# 2_waffling60-MX_matrix.net
KiCad netlist of a schematic drawn in Altium Designer
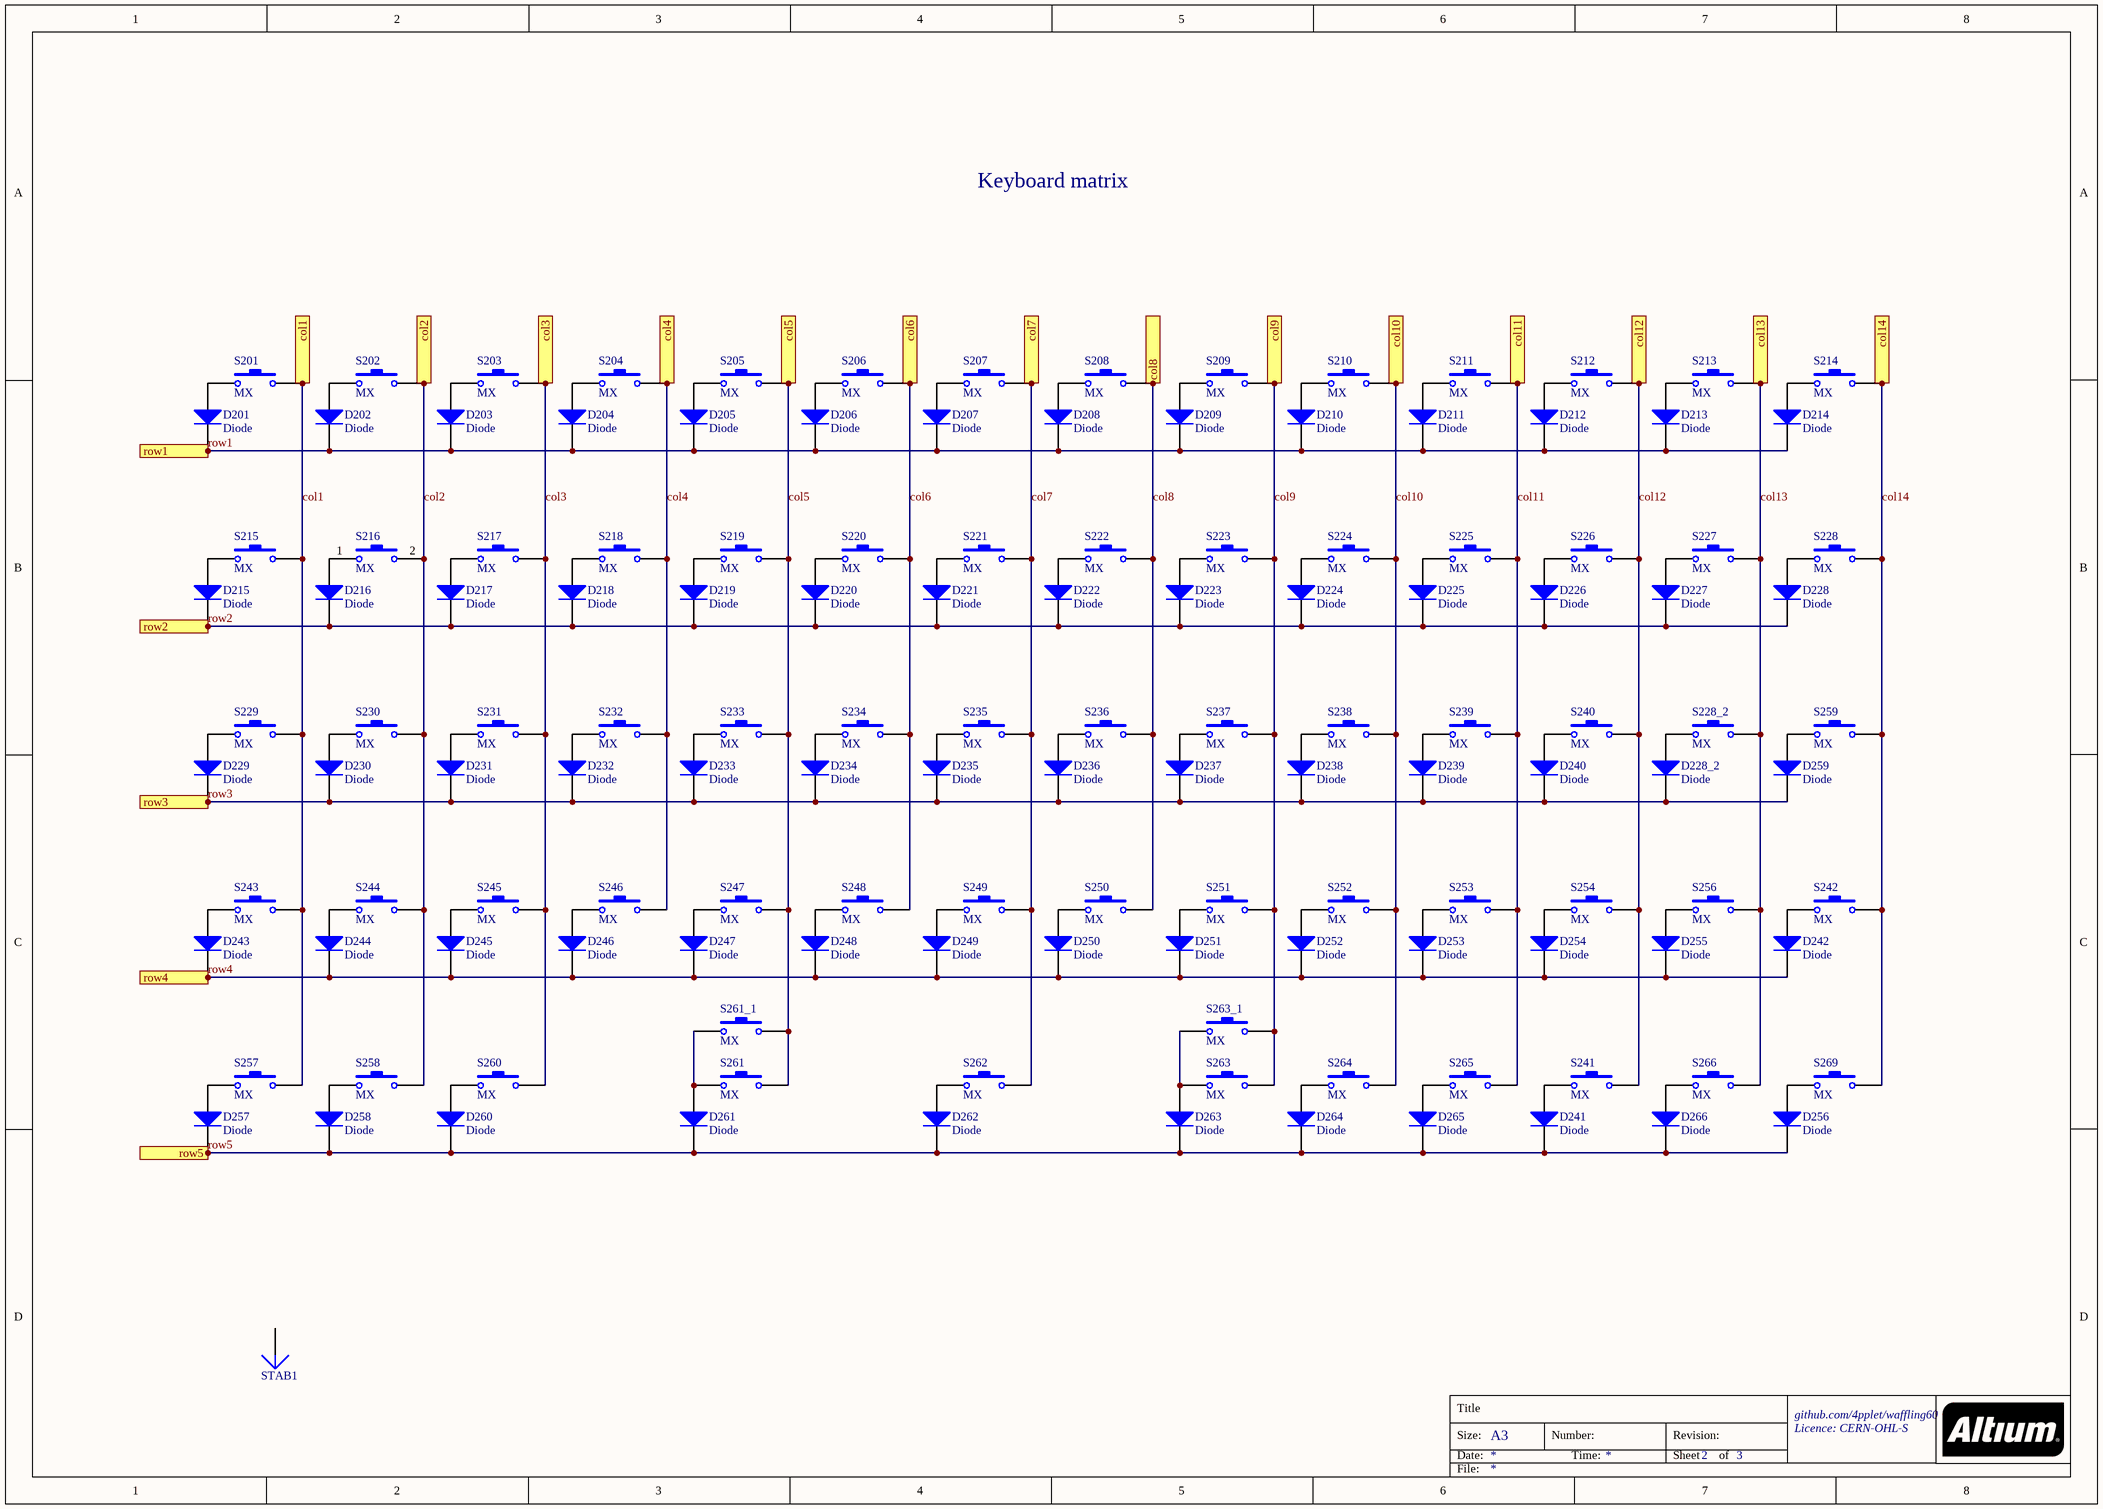
[diagram p0: 2_waffling60-MX_matrix.SchDoc]

(export (version "E")
  (design (tool "Eeschema 10.0.6"))
  (components
    (comp (ref "D201")
      (value "Diode")
      (footprint "SOD-123")
      (description "Default Diode")
      (fields (field (name "LCSC PART #") "C81598") (field (name "MRF.PART") "1N4148W"))
      (libsource (lib "Miscellaneous Devices") (part "Diode"))
    )
    (comp (ref "D202")
      (value "Diode")
      (footprint "SOD-123")
      (description "Default Diode")
      (fields (field (name "LCSC PART #") "C81598") (field (name "MRF.PART") "1N4148W"))
      (libsource (lib "Miscellaneous Devices") (part "Diode"))
    )
    (comp (ref "D203")
      (value "Diode")
      (footprint "SOD-123")
      (description "Default Diode")
      (fields (field (name "LCSC PART #") "C81598") (field (name "MRF.PART") "1N4148W"))
      (libsource (lib "Miscellaneous Devices") (part "Diode"))
    )
    (comp (ref "D204")
      (value "Diode")
      (footprint "SOD-123")
      (description "Default Diode")
      (fields (field (name "LCSC PART #") "C81598") (field (name "MRF.PART") "1N4148W"))
      (libsource (lib "Miscellaneous Devices") (part "Diode"))
    )
    (comp (ref "D205")
      (value "Diode")
      (footprint "SOD-123")
      (description "Default Diode")
      (fields (field (name "LCSC PART #") "C81598") (field (name "MRF.PART") "1N4148W"))
      (libsource (lib "Miscellaneous Devices") (part "Diode"))
    )
    (comp (ref "D206")
      (value "Diode")
      (footprint "SOD-123")
      (description "Default Diode")
      (fields (field (name "LCSC PART #") "C81598") (field (name "MRF.PART") "1N4148W"))
      (libsource (lib "Miscellaneous Devices") (part "Diode"))
    )
    (comp (ref "D207")
      (value "Diode")
      (footprint "SOD-123")
      (description "Default Diode")
      (fields (field (name "LCSC PART #") "C81598") (field (name "MRF.PART") "1N4148W"))
      (libsource (lib "Miscellaneous Devices") (part "Diode"))
    )
    (comp (ref "D208")
      (value "Diode")
      (footprint "SOD-123")
      (description "Default Diode")
      (fields (field (name "LCSC PART #") "C81598") (field (name "MRF.PART") "1N4148W"))
      (libsource (lib "Miscellaneous Devices") (part "Diode"))
    )
    (comp (ref "D209")
      (value "Diode")
      (footprint "SOD-123")
      (description "Default Diode")
      (fields (field (name "LCSC PART #") "C81598") (field (name "MRF.PART") "1N4148W"))
      (libsource (lib "Miscellaneous Devices") (part "Diode"))
    )
    (comp (ref "D210")
      (value "Diode")
      (footprint "SOD-123")
      (description "Default Diode")
      (fields (field (name "LCSC PART #") "C81598") (field (name "MRF.PART") "1N4148W"))
      (libsource (lib "Miscellaneous Devices") (part "Diode"))
    )
    (comp (ref "D211")
      (value "Diode")
      (footprint "SOD-123")
      (description "Default Diode")
      (fields (field (name "LCSC PART #") "C81598") (field (name "MRF.PART") "1N4148W"))
      (libsource (lib "Miscellaneous Devices") (part "Diode"))
    )
    (comp (ref "D212")
      (value "Diode")
      (footprint "SOD-123")
      (description "Default Diode")
      (fields (field (name "LCSC PART #") "C81598") (field (name "MRF.PART") "1N4148W"))
      (libsource (lib "Miscellaneous Devices") (part "Diode"))
    )
    (comp (ref "D213")
      (value "Diode")
      (footprint "SOD-123")
      (description "Default Diode")
      (fields (field (name "LCSC PART #") "C81598") (field (name "MRF.PART") "1N4148W"))
      (libsource (lib "Miscellaneous Devices") (part "Diode"))
    )
    (comp (ref "D214")
      (value "Diode")
      (footprint "SOD-123")
      (description "Default Diode")
      (fields (field (name "LCSC PART #") "C81598") (field (name "MRF.PART") "1N4148W"))
      (libsource (lib "Miscellaneous Devices") (part "Diode"))
    )
    (comp (ref "D215")
      (value "Diode")
      (footprint "SOD-123")
      (description "Default Diode")
      (fields (field (name "LCSC PART #") "C81598") (field (name "MRF.PART") "1N4148W"))
      (libsource (lib "Miscellaneous Devices") (part "Diode"))
    )
    (comp (ref "D216")
      (value "Diode")
      (footprint "SOD-123")
      (description "Default Diode")
      (fields (field (name "LCSC PART #") "C81598") (field (name "MRF.PART") "1N4148W"))
      (libsource (lib "Miscellaneous Devices") (part "Diode"))
    )
    (comp (ref "D217")
      (value "Diode")
      (footprint "SOD-123")
      (description "Default Diode")
      (fields (field (name "LCSC PART #") "C81598") (field (name "MRF.PART") "1N4148W"))
      (libsource (lib "Miscellaneous Devices") (part "Diode"))
    )
    (comp (ref "D218")
      (value "Diode")
      (footprint "SOD-123")
      (description "Default Diode")
      (fields (field (name "LCSC PART #") "C81598") (field (name "MRF.PART") "1N4148W"))
      (libsource (lib "Miscellaneous Devices") (part "Diode"))
    )
    (comp (ref "D219")
      (value "Diode")
      (footprint "SOD-123")
      (description "Default Diode")
      (fields (field (name "LCSC PART #") "C81598") (field (name "MRF.PART") "1N4148W"))
      (libsource (lib "Miscellaneous Devices") (part "Diode"))
    )
    (comp (ref "D220")
      (value "Diode")
      (footprint "SOD-123")
      (description "Default Diode")
      (fields (field (name "LCSC PART #") "C81598") (field (name "MRF.PART") "1N4148W"))
      (libsource (lib "Miscellaneous Devices") (part "Diode"))
    )
    (comp (ref "D221")
      (value "Diode")
      (footprint "SOD-123")
      (description "Default Diode")
      (fields (field (name "LCSC PART #") "C81598") (field (name "MRF.PART") "1N4148W"))
      (libsource (lib "Miscellaneous Devices") (part "Diode"))
    )
    (comp (ref "D222")
      (value "Diode")
      (footprint "SOD-123")
      (description "Default Diode")
      (fields (field (name "LCSC PART #") "C81598") (field (name "MRF.PART") "1N4148W"))
      (libsource (lib "Miscellaneous Devices") (part "Diode"))
    )
    (comp (ref "D223")
      (value "Diode")
      (footprint "SOD-123")
      (description "Default Diode")
      (fields (field (name "LCSC PART #") "C81598") (field (name "MRF.PART") "1N4148W"))
      (libsource (lib "Miscellaneous Devices") (part "Diode"))
    )
    (comp (ref "D224")
      (value "Diode")
      (footprint "SOD-123")
      (description "Default Diode")
      (fields (field (name "LCSC PART #") "C81598") (field (name "MRF.PART") "1N4148W"))
      (libsource (lib "Miscellaneous Devices") (part "Diode"))
    )
    (comp (ref "D225")
      (value "Diode")
      (footprint "SOD-123")
      (description "Default Diode")
      (fields (field (name "LCSC PART #") "C81598") (field (name "MRF.PART") "1N4148W"))
      (libsource (lib "Miscellaneous Devices") (part "Diode"))
    )
    (comp (ref "D226")
      (value "Diode")
      (footprint "SOD-123")
      (description "Default Diode")
      (fields (field (name "LCSC PART #") "C81598") (field (name "MRF.PART") "1N4148W"))
      (libsource (lib "Miscellaneous Devices") (part "Diode"))
    )
    (comp (ref "D227")
      (value "Diode")
      (footprint "SOD-123")
      (description "Default Diode")
      (fields (field (name "LCSC PART #") "C81598") (field (name "MRF.PART") "1N4148W"))
      (libsource (lib "Miscellaneous Devices") (part "Diode"))
    )
    (comp (ref "D228")
      (value "Diode")
      (footprint "SOD-123")
      (description "Default Diode")
      (fields (field (name "LCSC PART #") "C81598") (field (name "MRF.PART") "1N4148W"))
      (libsource (lib "Miscellaneous Devices") (part "Diode"))
    )
    (comp (ref "D228_2")
      (value "Diode")
      (footprint "SOD-123")
      (description "Default Diode")
      (fields (field (name "LCSC PART #") "C81598") (field (name "MRF.PART") "1N4148W"))
      (libsource (lib "Miscellaneous Devices") (part "Diode"))
    )
    (comp (ref "D229")
      (value "Diode")
      (footprint "SOD-123")
      (description "Default Diode")
      (fields (field (name "LCSC PART #") "C81598") (field (name "MRF.PART") "1N4148W"))
      (libsource (lib "Miscellaneous Devices") (part "Diode"))
    )
    (comp (ref "D230")
      (value "Diode")
      (footprint "SOD-123")
      (description "Default Diode")
      (fields (field (name "LCSC PART #") "C81598") (field (name "MRF.PART") "1N4148W"))
      (libsource (lib "Miscellaneous Devices") (part "Diode"))
    )
    (comp (ref "D231")
      (value "Diode")
      (footprint "SOD-123")
      (description "Default Diode")
      (fields (field (name "LCSC PART #") "C81598") (field (name "MRF.PART") "1N4148W"))
      (libsource (lib "Miscellaneous Devices") (part "Diode"))
    )
    (comp (ref "D232")
      (value "Diode")
      (footprint "SOD-123")
      (description "Default Diode")
      (fields (field (name "LCSC PART #") "C81598") (field (name "MRF.PART") "1N4148W"))
      (libsource (lib "Miscellaneous Devices") (part "Diode"))
    )
    (comp (ref "D233")
      (value "Diode")
      (footprint "SOD-123")
      (description "Default Diode")
      (fields (field (name "LCSC PART #") "C81598") (field (name "MRF.PART") "1N4148W"))
      (libsource (lib "Miscellaneous Devices") (part "Diode"))
    )
    (comp (ref "D234")
      (value "Diode")
      (footprint "SOD-123")
      (description "Default Diode")
      (fields (field (name "LCSC PART #") "C81598") (field (name "MRF.PART") "1N4148W"))
      (libsource (lib "Miscellaneous Devices") (part "Diode"))
    )
    (comp (ref "D235")
      (value "Diode")
      (footprint "SOD-123")
      (description "Default Diode")
      (fields (field (name "LCSC PART #") "C81598") (field (name "MRF.PART") "1N4148W"))
      (libsource (lib "Miscellaneous Devices") (part "Diode"))
    )
    (comp (ref "D236")
      (value "Diode")
      (footprint "SOD-123")
      (description "Default Diode")
      (fields (field (name "LCSC PART #") "C81598") (field (name "MRF.PART") "1N4148W"))
      (libsource (lib "Miscellaneous Devices") (part "Diode"))
    )
    (comp (ref "D237")
      (value "Diode")
      (footprint "SOD-123")
      (description "Default Diode")
      (fields (field (name "LCSC PART #") "C81598") (field (name "MRF.PART") "1N4148W"))
      (libsource (lib "Miscellaneous Devices") (part "Diode"))
    )
    (comp (ref "D238")
      (value "Diode")
      (footprint "SOD-123")
      (description "Default Diode")
      (fields (field (name "LCSC PART #") "C81598") (field (name "MRF.PART") "1N4148W"))
      (libsource (lib "Miscellaneous Devices") (part "Diode"))
    )
    (comp (ref "D239")
      (value "Diode")
      (footprint "SOD-123")
      (description "Default Diode")
      (fields (field (name "LCSC PART #") "C81598") (field (name "MRF.PART") "1N4148W"))
      (libsource (lib "Miscellaneous Devices") (part "Diode"))
    )
    (comp (ref "D240")
      (value "Diode")
      (footprint "SOD-123")
      (description "Default Diode")
      (fields (field (name "LCSC PART #") "C81598") (field (name "MRF.PART") "1N4148W"))
      (libsource (lib "Miscellaneous Devices") (part "Diode"))
    )
    (comp (ref "D241")
      (value "Diode")
      (footprint "SOD-123")
      (description "Default Diode")
      (fields (field (name "LCSC PART #") "C81598") (field (name "MRF.PART") "1N4148W"))
      (libsource (lib "Miscellaneous Devices") (part "Diode"))
    )
    (comp (ref "D242")
      (value "Diode")
      (footprint "SOD-123")
      (description "Default Diode")
      (fields (field (name "LCSC PART #") "C81598") (field (name "MRF.PART") "1N4148W"))
      (libsource (lib "Miscellaneous Devices") (part "Diode"))
    )
    (comp (ref "D243")
      (value "Diode")
      (footprint "SOD-123")
      (description "Default Diode")
      (fields (field (name "LCSC PART #") "C81598") (field (name "MRF.PART") "1N4148W"))
      (libsource (lib "Miscellaneous Devices") (part "Diode"))
    )
    (comp (ref "D244")
      (value "Diode")
      (footprint "SOD-123")
      (description "Default Diode")
      (fields (field (name "LCSC PART #") "C81598") (field (name "MRF.PART") "1N4148W"))
      (libsource (lib "Miscellaneous Devices") (part "Diode"))
    )
    (comp (ref "D245")
      (value "Diode")
      (footprint "SOD-123")
      (description "Default Diode")
      (fields (field (name "LCSC PART #") "C81598") (field (name "MRF.PART") "1N4148W"))
      (libsource (lib "Miscellaneous Devices") (part "Diode"))
    )
    (comp (ref "D246")
      (value "Diode")
      (footprint "SOD-123")
      (description "Default Diode")
      (fields (field (name "LCSC PART #") "C81598") (field (name "MRF.PART") "1N4148W"))
      (libsource (lib "Miscellaneous Devices") (part "Diode"))
    )
    (comp (ref "D247")
      (value "Diode")
      (footprint "SOD-123")
      (description "Default Diode")
      (fields (field (name "LCSC PART #") "C81598") (field (name "MRF.PART") "1N4148W"))
      (libsource (lib "Miscellaneous Devices") (part "Diode"))
    )
    (comp (ref "D248")
      (value "Diode")
      (footprint "SOD-123")
      (description "Default Diode")
      (fields (field (name "LCSC PART #") "C81598") (field (name "MRF.PART") "1N4148W"))
      (libsource (lib "Miscellaneous Devices") (part "Diode"))
    )
    (comp (ref "D249")
      (value "Diode")
      (footprint "SOD-123")
      (description "Default Diode")
      (fields (field (name "LCSC PART #") "C81598") (field (name "MRF.PART") "1N4148W"))
      (libsource (lib "Miscellaneous Devices") (part "Diode"))
    )
    (comp (ref "D250")
      (value "Diode")
      (footprint "SOD-123")
      (description "Default Diode")
      (fields (field (name "LCSC PART #") "C81598") (field (name "MRF.PART") "1N4148W"))
      (libsource (lib "Miscellaneous Devices") (part "Diode"))
    )
    (comp (ref "D251")
      (value "Diode")
      (footprint "SOD-123")
      (description "Default Diode")
      (fields (field (name "LCSC PART #") "C81598") (field (name "MRF.PART") "1N4148W"))
      (libsource (lib "Miscellaneous Devices") (part "Diode"))
    )
    (comp (ref "D252")
      (value "Diode")
      (footprint "SOD-123")
      (description "Default Diode")
      (fields (field (name "LCSC PART #") "C81598") (field (name "MRF.PART") "1N4148W"))
      (libsource (lib "Miscellaneous Devices") (part "Diode"))
    )
    (comp (ref "D253")
      (value "Diode")
      (footprint "SOD-123")
      (description "Default Diode")
      (fields (field (name "LCSC PART #") "C81598") (field (name "MRF.PART") "1N4148W"))
      (libsource (lib "Miscellaneous Devices") (part "Diode"))
    )
    (comp (ref "D254")
      (value "Diode")
      (footprint "SOD-123")
      (description "Default Diode")
      (fields (field (name "LCSC PART #") "C81598") (field (name "MRF.PART") "1N4148W"))
      (libsource (lib "Miscellaneous Devices") (part "Diode"))
    )
    (comp (ref "D255")
      (value "Diode")
      (footprint "SOD-123")
      (description "Default Diode")
      (fields (field (name "LCSC PART #") "C81598") (field (name "MRF.PART") "1N4148W"))
      (libsource (lib "Miscellaneous Devices") (part "Diode"))
    )
    (comp (ref "D256")
      (value "Diode")
      (footprint "SOD-123")
      (description "Default Diode")
      (fields (field (name "LCSC PART #") "C81598") (field (name "MRF.PART") "1N4148W"))
      (libsource (lib "Miscellaneous Devices") (part "Diode"))
    )
    (comp (ref "D257")
      (value "Diode")
      (footprint "SOD-123")
      (description "Default Diode")
      (fields (field (name "LCSC PART #") "C81598") (field (name "MRF.PART") "1N4148W"))
      (libsource (lib "Miscellaneous Devices") (part "Diode"))
    )
    (comp (ref "D258")
      (value "Diode")
      (footprint "SOD-123")
      (description "Default Diode")
      (fields (field (name "LCSC PART #") "C81598") (field (name "MRF.PART") "1N4148W"))
      (libsource (lib "Miscellaneous Devices") (part "Diode"))
    )
    (comp (ref "D259")
      (value "Diode")
      (footprint "SOD-123")
      (description "Default Diode")
      (fields (field (name "LCSC PART #") "C81598") (field (name "MRF.PART") "1N4148W"))
      (libsource (lib "Miscellaneous Devices") (part "Diode"))
    )
    (comp (ref "D260")
      (value "Diode")
      (footprint "SOD-123")
      (description "Default Diode")
      (fields (field (name "LCSC PART #") "C81598") (field (name "MRF.PART") "1N4148W"))
      (libsource (lib "Miscellaneous Devices") (part "Diode"))
    )
    (comp (ref "D261")
      (value "Diode")
      (footprint "SOD-123")
      (description "Default Diode")
      (fields (field (name "LCSC PART #") "C81598") (field (name "MRF.PART") "1N4148W"))
      (libsource (lib "Miscellaneous Devices") (part "Diode"))
    )
    (comp (ref "D262")
      (value "Diode")
      (footprint "SOD-123")
      (description "Default Diode")
      (fields (field (name "LCSC PART #") "C81598") (field (name "MRF.PART") "1N4148W"))
      (libsource (lib "Miscellaneous Devices") (part "Diode"))
    )
    (comp (ref "D263")
      (value "Diode")
      (footprint "SOD-123")
      (description "Default Diode")
      (fields (field (name "LCSC PART #") "C81598") (field (name "MRF.PART") "1N4148W"))
      (libsource (lib "Miscellaneous Devices") (part "Diode"))
    )
    (comp (ref "D264")
      (value "Diode")
      (footprint "SOD-123")
      (description "Default Diode")
      (fields (field (name "LCSC PART #") "C81598") (field (name "MRF.PART") "1N4148W"))
      (libsource (lib "Miscellaneous Devices") (part "Diode"))
    )
    (comp (ref "D265")
      (value "Diode")
      (footprint "SOD-123")
      (description "Default Diode")
      (fields (field (name "LCSC PART #") "C81598") (field (name "MRF.PART") "1N4148W"))
      (libsource (lib "Miscellaneous Devices") (part "Diode"))
    )
    (comp (ref "D266")
      (value "Diode")
      (footprint "SOD-123")
      (description "Default Diode")
      (fields (field (name "LCSC PART #") "C81598") (field (name "MRF.PART") "1N4148W"))
      (libsource (lib "Miscellaneous Devices") (part "Diode"))
    )
    (comp (ref "S201")
      (value "MX")
      (footprint "MX_ALPS-switch switche pol")
      (description "Switch")
      (libsource (lib "Miscellaneous Devices") (part "SW-PB"))
    )
    (comp (ref "S202")
      (value "MX")
      (footprint "MX_ALPS-switch - duplicate")
      (description "Switch")
      (libsource (lib "Miscellaneous Devices") (part "SW-PB"))
    )
    (comp (ref "S203")
      (value "MX")
      (footprint "MX_ALPS-switch switche pol")
      (description "Switch")
      (libsource (lib "Miscellaneous Devices") (part "SW-PB"))
    )
    (comp (ref "S204")
      (value "MX")
      (footprint "MX_ALPS-switch switche pol")
      (description "Switch")
      (libsource (lib "Miscellaneous Devices") (part "SW-PB"))
    )
    (comp (ref "S205")
      (value "MX")
      (footprint "MX_ALPS-switch switche pol")
      (description "Switch")
      (libsource (lib "Miscellaneous Devices") (part "SW-PB"))
    )
    (comp (ref "S206")
      (value "MX")
      (footprint "MX_ALPS-switch switche pol")
      (description "Switch")
      (libsource (lib "Miscellaneous Devices") (part "SW-PB"))
    )
    (comp (ref "S207")
      (value "MX")
      (footprint "MX_ALPS-switch switche pol")
      (description "Switch")
      (libsource (lib "Miscellaneous Devices") (part "SW-PB"))
    )
    (comp (ref "S208")
      (value "MX")
      (footprint "MX_ALPS-switch switche pol")
      (description "Switch")
      (libsource (lib "Miscellaneous Devices") (part "SW-PB"))
    )
    (comp (ref "S209")
      (value "MX")
      (footprint "MX_ALPS-switch switche pol")
      (description "Switch")
      (libsource (lib "Miscellaneous Devices") (part "SW-PB"))
    )
    (comp (ref "S210")
      (value "MX")
      (footprint "MX_ALPS-switch switche pol")
      (description "Switch")
      (libsource (lib "Miscellaneous Devices") (part "SW-PB"))
    )
    (comp (ref "S211")
      (value "MX")
      (footprint "MX_ALPS-switch switche pol")
      (description "Switch")
      (libsource (lib "Miscellaneous Devices") (part "SW-PB"))
    )
    (comp (ref "S212")
      (value "MX")
      (footprint "MX_ALPS-switch switche pol")
      (description "Switch")
      (libsource (lib "Miscellaneous Devices") (part "SW-PB"))
    )
    (comp (ref "S213")
      (value "MX")
      (footprint "MX_ALPS-switch switche pol")
      (description "Switch")
      (libsource (lib "Miscellaneous Devices") (part "SW-PB"))
    )
    (comp (ref "S214")
      (value "MX")
      (footprint "MX_ALPS-switch - duplicate")
      (description "Switch")
      (libsource (lib "Miscellaneous Devices") (part "SW-PB"))
    )
    (comp (ref "S215")
      (value "MX")
      (footprint "MX_ALPS-switch switche pol")
      (description "TAB")
      (libsource (lib "Miscellaneous Devices") (part "SW-PB"))
    )
    (comp (ref "S216")
      (value "MX")
      (footprint "MX_ALPS-switch - duplicate")
      (description "Switch")
      (libsource (lib "") (part "SW-PB_1"))
    )
    (comp (ref "S217")
      (value "MX")
      (footprint "MX_ALPS-switch switche pol")
      (description "Switch")
      (libsource (lib "Miscellaneous Devices") (part "SW-PB"))
    )
    (comp (ref "S218")
      (value "MX")
      (footprint "MX_ALPS-switch switche pol")
      (description "Switch")
      (libsource (lib "Miscellaneous Devices") (part "SW-PB"))
    )
    (comp (ref "S219")
      (value "MX")
      (footprint "MX_ALPS-switch switche pol")
      (description "Switch")
      (libsource (lib "Miscellaneous Devices") (part "SW-PB"))
    )
    (comp (ref "S220")
      (value "MX")
      (footprint "MX_ALPS-switch - duplicate")
      (description "Switch")
      (libsource (lib "Miscellaneous Devices") (part "SW-PB"))
    )
    (comp (ref "S221")
      (value "MX")
      (footprint "MX_ALPS-switch switche pol")
      (description "Switch")
      (libsource (lib "Miscellaneous Devices") (part "SW-PB"))
    )
    (comp (ref "S222")
      (value "MX")
      (footprint "MX_ALPS-switch - duplicate")
      (description "Switch")
      (libsource (lib "Miscellaneous Devices") (part "SW-PB"))
    )
    (comp (ref "S223")
      (value "MX")
      (footprint "MX_ALPS-switch switche pol")
      (description "Switch")
      (libsource (lib "Miscellaneous Devices") (part "SW-PB"))
    )
    (comp (ref "S224")
      (value "MX")
      (footprint "MX_ALPS-switch switche pol")
      (description "Switch")
      (libsource (lib "Miscellaneous Devices") (part "SW-PB"))
    )
    (comp (ref "S225")
      (value "MX")
      (footprint "MX_ALPS-switch switche pol")
      (description "Switch")
      (libsource (lib "Miscellaneous Devices") (part "SW-PB"))
    )
    (comp (ref "S226")
      (value "MX")
      (footprint "MX_ALPS-switch - duplicate")
      (description "Switch")
      (libsource (lib "Miscellaneous Devices") (part "SW-PB"))
    )
    (comp (ref "S227")
      (value "MX")
      (footprint "MX_ALPS-switch - duplicate")
      (description "Switch")
      (libsource (lib "Miscellaneous Devices") (part "SW-PB"))
    )
    (comp (ref "S228")
      (value "MX")
      (footprint "mx_alps - 1.5U")
      (description "Switch")
      (libsource (lib "Miscellaneous Devices") (part "SW-PB"))
    )
    (comp (ref "S228_2")
      (value "MX")
      (footprint "MX_ALPS-switch - duplicate")
      (description "Switch")
      (libsource (lib "Miscellaneous Devices") (part "SW-PB"))
    )
    (comp (ref "S229")
      (value "MX")
      (footprint "mx_alps - CAPS")
      (description "Switch")
      (libsource (lib "Miscellaneous Devices") (part "SW-PB"))
    )
    (comp (ref "S230")
      (value "MX")
      (footprint "MX_ALPS-switch - duplicate")
      (description "Switch")
      (libsource (lib "Miscellaneous Devices") (part "SW-PB"))
    )
    (comp (ref "S231")
      (value "MX")
      (footprint "MX_ALPS-switch switche pol")
      (description "Switch")
      (libsource (lib "Miscellaneous Devices") (part "SW-PB"))
    )
    (comp (ref "S232")
      (value "MX")
      (footprint "MX_ALPS-switch switche pol")
      (description "Switch")
      (libsource (lib "Miscellaneous Devices") (part "SW-PB"))
    )
    (comp (ref "S233")
      (value "MX")
      (footprint "MX_ALPS-switch switche pol")
      (description "Switch")
      (libsource (lib "Miscellaneous Devices") (part "SW-PB"))
    )
    (comp (ref "S234")
      (value "MX")
      (footprint "MX_ALPS-switch switche pol")
      (description "Switch")
      (libsource (lib "Miscellaneous Devices") (part "SW-PB"))
    )
    (comp (ref "S235")
      (value "MX")
      (footprint "MX_ALPS-switch switche pol")
      (description "Switch")
      (libsource (lib "Miscellaneous Devices") (part "SW-PB"))
    )
    (comp (ref "S236")
      (value "MX")
      (footprint "MX_ALPS-switch switche pol")
      (description "Switch")
      (libsource (lib "Miscellaneous Devices") (part "SW-PB"))
    )
    (comp (ref "S237")
      (value "MX")
      (footprint "MX_ALPS-switch switche pol")
      (description "Switch")
      (libsource (lib "Miscellaneous Devices") (part "SW-PB"))
    )
    (comp (ref "S238")
      (value "MX")
      (footprint "MX_ALPS-switch switche pol")
      (description "Switch")
      (libsource (lib "Miscellaneous Devices") (part "SW-PB"))
    )
    (comp (ref "S239")
      (value "MX")
      (footprint "MX_ALPS-switch switche pol")
      (description "Switch")
      (libsource (lib "Miscellaneous Devices") (part "SW-PB"))
    )
    (comp (ref "S240")
      (value "MX")
      (footprint "MX_ALPS-switch switche pol")
      (description "Switch")
      (libsource (lib "Miscellaneous Devices") (part "SW-PB"))
    )
    (comp (ref "S241")
      (value "MX")
      (footprint "mx_alps - 1u MOD-R")
      (description "Switch")
      (libsource (lib "Miscellaneous Devices") (part "SW-PB"))
    )
    (comp (ref "S242")
      (value "MX")
      (footprint "mx_alps - Enter - Rotated Stab")
      (description "Switch")
      (libsource (lib "Miscellaneous Devices") (part "SW-PB"))
    )
    (comp (ref "S243")
      (value "MX")
      (footprint "mx_alps - Left shift")
      (description "Switch")
      (libsource (lib "Miscellaneous Devices") (part "SW-PB"))
    )
    (comp (ref "S244")
      (value "MX")
      (footprint "MX_ALPS-switch")
      (description "Switch")
      (libsource (lib "Miscellaneous Devices") (part "SW-PB"))
    )
    (comp (ref "S245")
      (value "MX")
      (footprint "MX_ALPS-switch switche pol")
      (description "Switch")
      (libsource (lib "Miscellaneous Devices") (part "SW-PB"))
    )
    (comp (ref "S246")
      (value "MX")
      (footprint "MX_ALPS-switch switche pol")
      (description "Switch")
      (libsource (lib "Miscellaneous Devices") (part "SW-PB"))
    )
    (comp (ref "S247")
      (value "MX")
      (footprint "MX_ALPS-switch switche pol")
      (description "Switch")
      (libsource (lib "Miscellaneous Devices") (part "SW-PB"))
    )
    (comp (ref "S248")
      (value "MX")
      (footprint "MX_ALPS-switch switche pol")
      (description "Switch")
      (libsource (lib "Miscellaneous Devices") (part "SW-PB"))
    )
    (comp (ref "S249")
      (value "MX")
      (footprint "MX_ALPS-switch switche pol")
      (description "Switch")
      (libsource (lib "Miscellaneous Devices") (part "SW-PB"))
    )
    (comp (ref "S250")
      (value "MX")
      (footprint "MX_ALPS-switch switche pol")
      (description "Switch")
      (libsource (lib "Miscellaneous Devices") (part "SW-PB"))
    )
    (comp (ref "S251")
      (value "MX")
      (footprint "MX_ALPS-switch switche pol")
      (description "Switch")
      (libsource (lib "Miscellaneous Devices") (part "SW-PB"))
    )
    (comp (ref "S252")
      (value "MX")
      (footprint "MX_ALPS-switch switche pol")
      (description "Switch")
      (libsource (lib "Miscellaneous Devices") (part "SW-PB"))
    )
    (comp (ref "S253")
      (value "MX")
      (footprint "MX_ALPS-switch switche pol")
      (description "Switch")
      (libsource (lib "Miscellaneous Devices") (part "SW-PB"))
    )
    (comp (ref "S254")
      (value "MX")
      (footprint "MX_ALPS-switch switche pol")
      (description "Switch")
      (libsource (lib "Miscellaneous Devices") (part "SW-PB"))
    )
    (comp (ref "S256")
      (value "MX")
      (footprint "mx_alps- right shift")
      (description "Switch")
      (libsource (lib "Miscellaneous Devices") (part "SW-PB"))
    )
    (comp (ref "S257")
      (value "MX")
      (footprint "mx_alps- 1.5u MOD-L")
      (description "Switch")
      (libsource (lib "Miscellaneous Devices") (part "SW-PB"))
    )
    (comp (ref "S258")
      (value "MX")
      (footprint "mx_alps - 1u MOD-L")
      (description "Switch")
      (libsource (lib "Miscellaneous Devices") (part "SW-PB"))
    )
    (comp (ref "S259")
      (value "MX")
      (footprint "mx_alps - backspace")
      (description "Switch")
      (libsource (lib "Miscellaneous Devices") (part "SW-PB"))
    )
    (comp (ref "S260")
      (value "MX")
      (footprint "mx_alps- 1.5u MOD-L")
      (description "Switch")
      (libsource (lib "Miscellaneous Devices") (part "SW-PB"))
    )
    (comp (ref "S261")
      (value "MX")
      (footprint "MX-SWITCH - L SPLIT SPACE_V2")
      (description "Switch")
      (libsource (lib "Miscellaneous Devices") (part "SW-PB"))
    )
    (comp (ref "S261_1")
      (value "MX")
      (footprint "mx_alps - 3U - rotated stab")
      (description "Switch")
      (libsource (lib "Miscellaneous Devices") (part "SW-PB"))
    )
    (comp (ref "S262")
      (value "MX")
      (footprint "MX-switch - Space_V3")
      (description "Switch")
      (libsource (lib "Miscellaneous Devices") (part "SW-PB"))
    )
    (comp (ref "S263")
      (value "MX")
      (footprint "MX-SWITCH - R SPLIT SPACE_V2")
      (description "Switch")
      (libsource (lib "Miscellaneous Devices") (part "SW-PB"))
    )
    (comp (ref "S263_1")
      (value "MX")
      (footprint "mx_alps - 3U - rotated stab")
      (description "Switch")
      (libsource (lib "Miscellaneous Devices") (part "SW-PB"))
    )
    (comp (ref "S264")
      (value "MX")
      (footprint "MX_ALPS-switch switche pol")
      (description "Switch")
      (libsource (lib "Miscellaneous Devices") (part "SW-PB"))
    )
    (comp (ref "S265")
      (value "MX")
      (footprint "mx_alps - 1.5u MOD-R")
      (description "Switch")
      (libsource (lib "Miscellaneous Devices") (part "SW-PB"))
    )
    (comp (ref "S266")
      (value "MX")
      (footprint "mx_alps - 1.5u MOD-R")
      (description "Switch")
      (libsource (lib "Miscellaneous Devices") (part "SW-PB"))
    )
    (comp (ref "S269")
      (value "MX")
      (footprint "MX_ALPS-switch - duplicate")
      (description "Switch")
      (libsource (lib "Miscellaneous Devices") (part "SW-PB"))
    )
    (comp (ref "STAB1")
      (value "Plug")
      (footprint "Stab 10U")
      (libsource (lib "Miscellaneous Connectors") (part "Plug"))
    )
  )
  (nets
    (net (code "1") (name "/col1") (class "Default")
      (node (ref "S201") (pin "2") (pinfunction "2_2") (pintype "passive"))
      (node (ref "S215") (pin "2") (pinfunction "2_2") (pintype "passive"))
      (node (ref "S229") (pin "1") (pinfunction "1_1") (pintype "passive"))
      (node (ref "S243") (pin "2") (pinfunction "2_2") (pintype "passive"))
      (node (ref "S257") (pin "1") (pinfunction "1_1") (pintype "passive"))
    )
    (net (code "2") (name "/col2") (class "Default")
      (node (ref "S202") (pin "2") (pinfunction "2_2") (pintype "passive"))
      (node (ref "S216") (pin "2") (pinfunction "2_2") (pintype "passive"))
      (node (ref "S230") (pin "2") (pinfunction "2_2") (pintype "passive"))
      (node (ref "S244") (pin "1") (pinfunction "1_1") (pintype "passive"))
      (node (ref "S258") (pin "2") (pinfunction "2_2") (pintype "passive"))
    )
    (net (code "3") (name "/col3") (class "Default")
      (node (ref "S203") (pin "2") (pinfunction "2_2") (pintype "passive"))
      (node (ref "S217") (pin "2") (pinfunction "2_2") (pintype "passive"))
      (node (ref "S231") (pin "2") (pinfunction "2_2") (pintype "passive"))
      (node (ref "S245") (pin "2") (pinfunction "2_2") (pintype "passive"))
      (node (ref "S260") (pin "2") (pinfunction "2_2") (pintype "passive"))
    )
    (net (code "4") (name "/col4") (class "Default")
      (node (ref "S204") (pin "2") (pinfunction "2_2") (pintype "passive"))
      (node (ref "S218") (pin "2") (pinfunction "2_2") (pintype "passive"))
      (node (ref "S232") (pin "2") (pinfunction "2_2") (pintype "passive"))
      (node (ref "S246") (pin "2") (pinfunction "2_2") (pintype "passive"))
    )
    (net (code "5") (name "/col5") (class "Default")
      (node (ref "S205") (pin "2") (pinfunction "2_2") (pintype "passive"))
      (node (ref "S219") (pin "2") (pinfunction "2_2") (pintype "passive"))
      (node (ref "S233") (pin "2") (pinfunction "2_2") (pintype "passive"))
      (node (ref "S247") (pin "2") (pinfunction "2_2") (pintype "passive"))
      (node (ref "S261") (pin "2") (pinfunction "2_2") (pintype "passive"))
      (node (ref "S261_1") (pin "2") (pinfunction "2_2") (pintype "passive"))
    )
    (net (code "6") (name "/col6") (class "Default")
      (node (ref "S206") (pin "2") (pinfunction "2_2") (pintype "passive"))
      (node (ref "S220") (pin "2") (pinfunction "2_2") (pintype "passive"))
      (node (ref "S234") (pin "2") (pinfunction "2_2") (pintype "passive"))
      (node (ref "S248") (pin "2") (pinfunction "2_2") (pintype "passive"))
    )
    (net (code "7") (name "/col7") (class "Default")
      (node (ref "S207") (pin "2") (pinfunction "2_2") (pintype "passive"))
      (node (ref "S221") (pin "2") (pinfunction "2_2") (pintype "passive"))
      (node (ref "S235") (pin "2") (pinfunction "2_2") (pintype "passive"))
      (node (ref "S249") (pin "2") (pinfunction "2_2") (pintype "passive"))
      (node (ref "S262") (pin "1") (pinfunction "1_1") (pintype "passive"))
    )
    (net (code "8") (name "/col8") (class "Default")
      (node (ref "S208") (pin "2") (pinfunction "2_2") (pintype "passive"))
      (node (ref "S222") (pin "2") (pinfunction "2_2") (pintype "passive"))
      (node (ref "S236") (pin "2") (pinfunction "2_2") (pintype "passive"))
      (node (ref "S250") (pin "2") (pinfunction "2_2") (pintype "passive"))
    )
    (net (code "9") (name "/col9") (class "Default")
      (node (ref "S209") (pin "2") (pinfunction "2_2") (pintype "passive"))
      (node (ref "S223") (pin "2") (pinfunction "2_2") (pintype "passive"))
      (node (ref "S237") (pin "2") (pinfunction "2_2") (pintype "passive"))
      (node (ref "S251") (pin "2") (pinfunction "2_2") (pintype "passive"))
      (node (ref "S263") (pin "1") (pinfunction "1_1") (pintype "passive"))
      (node (ref "S263_1") (pin "1") (pinfunction "1_1") (pintype "passive"))
    )
    (net (code "10") (name "/col10") (class "Default")
      (node (ref "S210") (pin "2") (pinfunction "2_2") (pintype "passive"))
      (node (ref "S224") (pin "2") (pinfunction "2_2") (pintype "passive"))
      (node (ref "S238") (pin "2") (pinfunction "2_2") (pintype "passive"))
      (node (ref "S252") (pin "2") (pinfunction "2_2") (pintype "passive"))
      (node (ref "S264") (pin "2") (pinfunction "2_2") (pintype "passive"))
    )
    (net (code "11") (name "/col11") (class "Default")
      (node (ref "S211") (pin "2") (pinfunction "2_2") (pintype "passive"))
      (node (ref "S225") (pin "2") (pinfunction "2_2") (pintype "passive"))
      (node (ref "S239") (pin "2") (pinfunction "2_2") (pintype "passive"))
      (node (ref "S253") (pin "2") (pinfunction "2_2") (pintype "passive"))
      (node (ref "S265") (pin "1") (pinfunction "1_1") (pintype "passive"))
    )
    (net (code "12") (name "/col12") (class "Default")
      (node (ref "S212") (pin "2") (pinfunction "2_2") (pintype "passive"))
      (node (ref "S226") (pin "2") (pinfunction "2_2") (pintype "passive"))
      (node (ref "S240") (pin "2") (pinfunction "2_2") (pintype "passive"))
      (node (ref "S241") (pin "1") (pinfunction "1_1") (pintype "passive"))
      (node (ref "S254") (pin "2") (pinfunction "2_2") (pintype "passive"))
    )
    (net (code "13") (name "/col13") (class "Default")
      (node (ref "S213") (pin "2") (pinfunction "2_2") (pintype "passive"))
      (node (ref "S227") (pin "2") (pinfunction "2_2") (pintype "passive"))
      (node (ref "S228_2") (pin "2") (pinfunction "2_2") (pintype "passive"))
      (node (ref "S256") (pin "2") (pinfunction "2_2") (pintype "passive"))
      (node (ref "S266") (pin "2") (pinfunction "2_2") (pintype "passive"))
    )
    (net (code "14") (name "/col14") (class "Default")
      (node (ref "S214") (pin "2") (pinfunction "2_2") (pintype "passive"))
      (node (ref "S228") (pin "2") (pinfunction "2_2") (pintype "passive"))
      (node (ref "S242") (pin "2") (pinfunction "2_2") (pintype "passive"))
      (node (ref "S259") (pin "2") (pinfunction "2_2") (pintype "passive"))
      (node (ref "S269") (pin "2") (pinfunction "2_2") (pintype "passive"))
    )
    (net (code "15") (name "/row1") (class "Default")
      (node (ref "D201") (pin "2") (pinfunction "K_2") (pintype "passive"))
      (node (ref "D202") (pin "2") (pinfunction "K_2") (pintype "passive"))
      (node (ref "D203") (pin "2") (pinfunction "K_2") (pintype "passive"))
      (node (ref "D204") (pin "2") (pinfunction "K_2") (pintype "passive"))
      (node (ref "D205") (pin "2") (pinfunction "K_2") (pintype "passive"))
      (node (ref "D206") (pin "2") (pinfunction "K_2") (pintype "passive"))
      (node (ref "D207") (pin "2") (pinfunction "K_2") (pintype "passive"))
      (node (ref "D208") (pin "2") (pinfunction "K_2") (pintype "passive"))
      (node (ref "D209") (pin "2") (pinfunction "K_2") (pintype "passive"))
      (node (ref "D210") (pin "2") (pinfunction "K_2") (pintype "passive"))
      (node (ref "D211") (pin "2") (pinfunction "K_2") (pintype "passive"))
      (node (ref "D212") (pin "2") (pinfunction "K_2") (pintype "passive"))
      (node (ref "D213") (pin "2") (pinfunction "K_2") (pintype "passive"))
      (node (ref "D214") (pin "2") (pinfunction "K_2") (pintype "passive"))
    )
    (net (code "16") (name "/row2") (class "Default")
      (node (ref "D215") (pin "2") (pinfunction "K_2") (pintype "passive"))
      (node (ref "D216") (pin "2") (pinfunction "K_2") (pintype "passive"))
      (node (ref "D217") (pin "2") (pinfunction "K_2") (pintype "passive"))
      (node (ref "D218") (pin "2") (pinfunction "K_2") (pintype "passive"))
      (node (ref "D219") (pin "2") (pinfunction "K_2") (pintype "passive"))
      (node (ref "D220") (pin "2") (pinfunction "K_2") (pintype "passive"))
      (node (ref "D221") (pin "2") (pinfunction "K_2") (pintype "passive"))
      (node (ref "D222") (pin "2") (pinfunction "K_2") (pintype "passive"))
      (node (ref "D223") (pin "2") (pinfunction "K_2") (pintype "passive"))
      (node (ref "D224") (pin "2") (pinfunction "K_2") (pintype "passive"))
      (node (ref "D225") (pin "2") (pinfunction "K_2") (pintype "passive"))
      (node (ref "D226") (pin "2") (pinfunction "K_2") (pintype "passive"))
      (node (ref "D227") (pin "2") (pinfunction "K_2") (pintype "passive"))
      (node (ref "D228") (pin "2") (pinfunction "K_2") (pintype "passive"))
    )
    (net (code "17") (name "/row3") (class "Default")
      (node (ref "D228_2") (pin "2") (pinfunction "K_2") (pintype "passive"))
      (node (ref "D229") (pin "2") (pinfunction "K_2") (pintype "passive"))
      (node (ref "D230") (pin "2") (pinfunction "K_2") (pintype "passive"))
      (node (ref "D231") (pin "2") (pinfunction "K_2") (pintype "passive"))
      (node (ref "D232") (pin "2") (pinfunction "K_2") (pintype "passive"))
      (node (ref "D233") (pin "2") (pinfunction "K_2") (pintype "passive"))
      (node (ref "D234") (pin "2") (pinfunction "K_2") (pintype "passive"))
      (node (ref "D235") (pin "2") (pinfunction "K_2") (pintype "passive"))
      (node (ref "D236") (pin "2") (pinfunction "K_2") (pintype "passive"))
      (node (ref "D237") (pin "2") (pinfunction "K_2") (pintype "passive"))
      (node (ref "D238") (pin "2") (pinfunction "K_2") (pintype "passive"))
      (node (ref "D239") (pin "2") (pinfunction "K_2") (pintype "passive"))
      (node (ref "D240") (pin "2") (pinfunction "K_2") (pintype "passive"))
      (node (ref "D259") (pin "2") (pinfunction "K_2") (pintype "passive"))
    )
    (net (code "18") (name "/row4") (class "Default")
      (node (ref "D242") (pin "2") (pinfunction "K_2") (pintype "passive"))
      (node (ref "D243") (pin "2") (pinfunction "K_2") (pintype "passive"))
      (node (ref "D244") (pin "2") (pinfunction "K_2") (pintype "passive"))
      (node (ref "D245") (pin "2") (pinfunction "K_2") (pintype "passive"))
      (node (ref "D246") (pin "2") (pinfunction "K_2") (pintype "passive"))
      (node (ref "D247") (pin "2") (pinfunction "K_2") (pintype "passive"))
      (node (ref "D248") (pin "2") (pinfunction "K_2") (pintype "passive"))
      (node (ref "D249") (pin "2") (pinfunction "K_2") (pintype "passive"))
      (node (ref "D250") (pin "2") (pinfunction "K_2") (pintype "passive"))
      (node (ref "D251") (pin "2") (pinfunction "K_2") (pintype "passive"))
      (node (ref "D252") (pin "2") (pinfunction "K_2") (pintype "passive"))
      (node (ref "D253") (pin "2") (pinfunction "K_2") (pintype "passive"))
      (node (ref "D254") (pin "2") (pinfunction "K_2") (pintype "passive"))
      (node (ref "D255") (pin "2") (pinfunction "K_2") (pintype "passive"))
    )
    (net (code "19") (name "/row5") (class "Default")
      (node (ref "D241") (pin "2") (pinfunction "K_2") (pintype "passive"))
      (node (ref "D256") (pin "2") (pinfunction "K_2") (pintype "passive"))
      (node (ref "D257") (pin "2") (pinfunction "K_2") (pintype "passive"))
      (node (ref "D258") (pin "2") (pinfunction "K_2") (pintype "passive"))
      (node (ref "D260") (pin "2") (pinfunction "K_2") (pintype "passive"))
      (node (ref "D261") (pin "2") (pinfunction "K_2") (pintype "passive"))
      (node (ref "D262") (pin "2") (pinfunction "K_2") (pintype "passive"))
      (node (ref "D263") (pin "2") (pinfunction "K_2") (pintype "passive"))
      (node (ref "D264") (pin "2") (pinfunction "K_2") (pintype "passive"))
      (node (ref "D265") (pin "2") (pinfunction "K_2") (pintype "passive"))
      (node (ref "D266") (pin "2") (pinfunction "K_2") (pintype "passive"))
    )
    (net (code "20") (name "Net-(D201-A)") (class "Default")
      (node (ref "D201") (pin "1") (pinfunction "A_1") (pintype "passive"))
      (node (ref "S201") (pin "1") (pinfunction "1_1") (pintype "passive"))
    )
    (net (code "21") (name "Net-(D202-A)") (class "Default")
      (node (ref "D202") (pin "1") (pinfunction "A_1") (pintype "passive"))
      (node (ref "S202") (pin "1") (pinfunction "1_1") (pintype "passive"))
    )
    (net (code "22") (name "Net-(D203-A)") (class "Default")
      (node (ref "D203") (pin "1") (pinfunction "A_1") (pintype "passive"))
      (node (ref "S203") (pin "1") (pinfunction "1_1") (pintype "passive"))
    )
    (net (code "23") (name "Net-(D204-A)") (class "Default")
      (node (ref "D204") (pin "1") (pinfunction "A_1") (pintype "passive"))
      (node (ref "S204") (pin "1") (pinfunction "1_1") (pintype "passive"))
    )
    (net (code "24") (name "Net-(D205-A)") (class "Default")
      (node (ref "D205") (pin "1") (pinfunction "A_1") (pintype "passive"))
      (node (ref "S205") (pin "1") (pinfunction "1_1") (pintype "passive"))
    )
    (net (code "25") (name "Net-(D206-A)") (class "Default")
      (node (ref "D206") (pin "1") (pinfunction "A_1") (pintype "passive"))
      (node (ref "S206") (pin "1") (pinfunction "1_1") (pintype "passive"))
    )
    (net (code "26") (name "Net-(D207-A)") (class "Default")
      (node (ref "D207") (pin "1") (pinfunction "A_1") (pintype "passive"))
      (node (ref "S207") (pin "1") (pinfunction "1_1") (pintype "passive"))
    )
    (net (code "27") (name "Net-(D208-A)") (class "Default")
      (node (ref "D208") (pin "1") (pinfunction "A_1") (pintype "passive"))
      (node (ref "S208") (pin "1") (pinfunction "1_1") (pintype "passive"))
    )
    (net (code "28") (name "Net-(D209-A)") (class "Default")
      (node (ref "D209") (pin "1") (pinfunction "A_1") (pintype "passive"))
      (node (ref "S209") (pin "1") (pinfunction "1_1") (pintype "passive"))
    )
    (net (code "29") (name "Net-(D210-A)") (class "Default")
      (node (ref "D210") (pin "1") (pinfunction "A_1") (pintype "passive"))
      (node (ref "S210") (pin "1") (pinfunction "1_1") (pintype "passive"))
    )
    (net (code "30") (name "Net-(D211-A)") (class "Default")
      (node (ref "D211") (pin "1") (pinfunction "A_1") (pintype "passive"))
      (node (ref "S211") (pin "1") (pinfunction "1_1") (pintype "passive"))
    )
    (net (code "31") (name "Net-(D212-A)") (class "Default")
      (node (ref "D212") (pin "1") (pinfunction "A_1") (pintype "passive"))
      (node (ref "S212") (pin "1") (pinfunction "1_1") (pintype "passive"))
    )
    (net (code "32") (name "Net-(D213-A)") (class "Default")
      (node (ref "D213") (pin "1") (pinfunction "A_1") (pintype "passive"))
      (node (ref "S213") (pin "1") (pinfunction "1_1") (pintype "passive"))
    )
    (net (code "33") (name "Net-(D214-A)") (class "Default")
      (node (ref "D214") (pin "1") (pinfunction "A_1") (pintype "passive"))
      (node (ref "S214") (pin "1") (pinfunction "1_1") (pintype "passive"))
    )
    (net (code "34") (name "Net-(D215-A)") (class "Default")
      (node (ref "D215") (pin "1") (pinfunction "A_1") (pintype "passive"))
      (node (ref "S215") (pin "1") (pinfunction "1_1") (pintype "passive"))
    )
    (net (code "35") (name "Net-(D216-A)") (class "Default")
      (node (ref "D216") (pin "1") (pinfunction "A_1") (pintype "passive"))
      (node (ref "S216") (pin "1") (pinfunction "1_1") (pintype "passive"))
    )
    (net (code "36") (name "Net-(D217-A)") (class "Default")
      (node (ref "D217") (pin "1") (pinfunction "A_1") (pintype "passive"))
      (node (ref "S217") (pin "1") (pinfunction "1_1") (pintype "passive"))
    )
    (net (code "37") (name "Net-(D218-A)") (class "Default")
      (node (ref "D218") (pin "1") (pinfunction "A_1") (pintype "passive"))
      (node (ref "S218") (pin "1") (pinfunction "1_1") (pintype "passive"))
    )
    (net (code "38") (name "Net-(D219-A)") (class "Default")
      (node (ref "D219") (pin "1") (pinfunction "A_1") (pintype "passive"))
      (node (ref "S219") (pin "1") (pinfunction "1_1") (pintype "passive"))
    )
    (net (code "39") (name "Net-(D220-A)") (class "Default")
      (node (ref "D220") (pin "1") (pinfunction "A_1") (pintype "passive"))
      (node (ref "S220") (pin "1") (pinfunction "1_1") (pintype "passive"))
    )
    (net (code "40") (name "Net-(D221-A)") (class "Default")
      (node (ref "D221") (pin "1") (pinfunction "A_1") (pintype "passive"))
      (node (ref "S221") (pin "1") (pinfunction "1_1") (pintype "passive"))
    )
    (net (code "41") (name "Net-(D222-A)") (class "Default")
      (node (ref "D222") (pin "1") (pinfunction "A_1") (pintype "passive"))
      (node (ref "S222") (pin "1") (pinfunction "1_1") (pintype "passive"))
    )
    (net (code "42") (name "Net-(D223-A)") (class "Default")
      (node (ref "D223") (pin "1") (pinfunction "A_1") (pintype "passive"))
      (node (ref "S223") (pin "1") (pinfunction "1_1") (pintype "passive"))
    )
    (net (code "43") (name "Net-(D224-A)") (class "Default")
      (node (ref "D224") (pin "1") (pinfunction "A_1") (pintype "passive"))
      (node (ref "S224") (pin "1") (pinfunction "1_1") (pintype "passive"))
    )
    (net (code "44") (name "Net-(D225-A)") (class "Default")
      (node (ref "D225") (pin "1") (pinfunction "A_1") (pintype "passive"))
      (node (ref "S225") (pin "1") (pinfunction "1_1") (pintype "passive"))
    )
    (net (code "45") (name "Net-(D226-A)") (class "Default")
      (node (ref "D226") (pin "1") (pinfunction "A_1") (pintype "passive"))
      (node (ref "S226") (pin "1") (pinfunction "1_1") (pintype "passive"))
    )
    (net (code "46") (name "Net-(D227-A)") (class "Default")
      (node (ref "D227") (pin "1") (pinfunction "A_1") (pintype "passive"))
      (node (ref "S227") (pin "1") (pinfunction "1_1") (pintype "passive"))
    )
    (net (code "47") (name "Net-(D228-A)") (class "Default")
      (node (ref "D228") (pin "1") (pinfunction "A_1") (pintype "passive"))
      (node (ref "S228") (pin "1") (pinfunction "1_1") (pintype "passive"))
    )
    (net (code "48") (name "Net-(D228_2-A)") (class "Default")
      (node (ref "D228_2") (pin "1") (pinfunction "A_1") (pintype "passive"))
      (node (ref "S228_2") (pin "1") (pinfunction "1_1") (pintype "passive"))
    )
    (net (code "49") (name "Net-(D229-A)") (class "Default")
      (node (ref "D229") (pin "1") (pinfunction "A_1") (pintype "passive"))
      (node (ref "S229") (pin "2") (pinfunction "2_2") (pintype "passive"))
    )
    (net (code "50") (name "Net-(D230-A)") (class "Default")
      (node (ref "D230") (pin "1") (pinfunction "A_1") (pintype "passive"))
      (node (ref "S230") (pin "1") (pinfunction "1_1") (pintype "passive"))
    )
    (net (code "51") (name "Net-(D231-A)") (class "Default")
      (node (ref "D231") (pin "1") (pinfunction "A_1") (pintype "passive"))
      (node (ref "S231") (pin "1") (pinfunction "1_1") (pintype "passive"))
    )
    (net (code "52") (name "Net-(D232-A)") (class "Default")
      (node (ref "D232") (pin "1") (pinfunction "A_1") (pintype "passive"))
      (node (ref "S232") (pin "1") (pinfunction "1_1") (pintype "passive"))
    )
    (net (code "53") (name "Net-(D233-A)") (class "Default")
      (node (ref "D233") (pin "1") (pinfunction "A_1") (pintype "passive"))
      (node (ref "S233") (pin "1") (pinfunction "1_1") (pintype "passive"))
    )
    (net (code "54") (name "Net-(D234-A)") (class "Default")
      (node (ref "D234") (pin "1") (pinfunction "A_1") (pintype "passive"))
      (node (ref "S234") (pin "1") (pinfunction "1_1") (pintype "passive"))
    )
    (net (code "55") (name "Net-(D235-A)") (class "Default")
      (node (ref "D235") (pin "1") (pinfunction "A_1") (pintype "passive"))
      (node (ref "S235") (pin "1") (pinfunction "1_1") (pintype "passive"))
    )
    (net (code "56") (name "Net-(D236-A)") (class "Default")
      (node (ref "D236") (pin "1") (pinfunction "A_1") (pintype "passive"))
      (node (ref "S236") (pin "1") (pinfunction "1_1") (pintype "passive"))
    )
    (net (code "57") (name "Net-(D237-A)") (class "Default")
      (node (ref "D237") (pin "1") (pinfunction "A_1") (pintype "passive"))
      (node (ref "S237") (pin "1") (pinfunction "1_1") (pintype "passive"))
    )
    (net (code "58") (name "Net-(D238-A)") (class "Default")
      (node (ref "D238") (pin "1") (pinfunction "A_1") (pintype "passive"))
      (node (ref "S238") (pin "1") (pinfunction "1_1") (pintype "passive"))
    )
    (net (code "59") (name "Net-(D239-A)") (class "Default")
      (node (ref "D239") (pin "1") (pinfunction "A_1") (pintype "passive"))
      (node (ref "S239") (pin "1") (pinfunction "1_1") (pintype "passive"))
    )
    (net (code "60") (name "Net-(D240-A)") (class "Default")
      (node (ref "D240") (pin "1") (pinfunction "A_1") (pintype "passive"))
      (node (ref "S240") (pin "1") (pinfunction "1_1") (pintype "passive"))
    )
    (net (code "61") (name "Net-(D241-A)") (class "Default")
      (node (ref "D241") (pin "1") (pinfunction "A_1") (pintype "passive"))
      (node (ref "S241") (pin "2") (pinfunction "2_2") (pintype "passive"))
    )
    (net (code "62") (name "Net-(D242-A)") (class "Default")
      (node (ref "D242") (pin "1") (pinfunction "A_1") (pintype "passive"))
      (node (ref "S242") (pin "1") (pinfunction "1_1") (pintype "passive"))
    )
    (net (code "63") (name "Net-(D243-A)") (class "Default")
      (node (ref "D243") (pin "1") (pinfunction "A_1") (pintype "passive"))
      (node (ref "S243") (pin "1") (pinfunction "1_1") (pintype "passive"))
    )
    (net (code "64") (name "Net-(D244-A)") (class "Default")
      (node (ref "D244") (pin "1") (pinfunction "A_1") (pintype "passive"))
      (node (ref "S244") (pin "2") (pinfunction "2_2") (pintype "passive"))
    )
    (net (code "65") (name "Net-(D245-A)") (class "Default")
      (node (ref "D245") (pin "1") (pinfunction "A_1") (pintype "passive"))
      (node (ref "S245") (pin "1") (pinfunction "1_1") (pintype "passive"))
    )
    (net (code "66") (name "Net-(D246-A)") (class "Default")
      (node (ref "D246") (pin "1") (pinfunction "A_1") (pintype "passive"))
      (node (ref "S246") (pin "1") (pinfunction "1_1") (pintype "passive"))
    )
    (net (code "67") (name "Net-(D247-A)") (class "Default")
      (node (ref "D247") (pin "1") (pinfunction "A_1") (pintype "passive"))
      (node (ref "S247") (pin "1") (pinfunction "1_1") (pintype "passive"))
    )
    (net (code "68") (name "Net-(D248-A)") (class "Default")
      (node (ref "D248") (pin "1") (pinfunction "A_1") (pintype "passive"))
      (node (ref "S248") (pin "1") (pinfunction "1_1") (pintype "passive"))
    )
    (net (code "69") (name "Net-(D249-A)") (class "Default")
      (node (ref "D249") (pin "1") (pinfunction "A_1") (pintype "passive"))
      (node (ref "S249") (pin "1") (pinfunction "1_1") (pintype "passive"))
    )
    (net (code "70") (name "Net-(D250-A)") (class "Default")
      (node (ref "D250") (pin "1") (pinfunction "A_1") (pintype "passive"))
      (node (ref "S250") (pin "1") (pinfunction "1_1") (pintype "passive"))
    )
    (net (code "71") (name "Net-(D251-A)") (class "Default")
      (node (ref "D251") (pin "1") (pinfunction "A_1") (pintype "passive"))
      (node (ref "S251") (pin "1") (pinfunction "1_1") (pintype "passive"))
    )
    (net (code "72") (name "Net-(D252-A)") (class "Default")
      (node (ref "D252") (pin "1") (pinfunction "A_1") (pintype "passive"))
      (node (ref "S252") (pin "1") (pinfunction "1_1") (pintype "passive"))
    )
    (net (code "73") (name "Net-(D253-A)") (class "Default")
      (node (ref "D253") (pin "1") (pinfunction "A_1") (pintype "passive"))
      (node (ref "S253") (pin "1") (pinfunction "1_1") (pintype "passive"))
    )
    (net (code "74") (name "Net-(D254-A)") (class "Default")
      (node (ref "D254") (pin "1") (pinfunction "A_1") (pintype "passive"))
      (node (ref "S254") (pin "1") (pinfunction "1_1") (pintype "passive"))
    )
    (net (code "75") (name "Net-(D255-A)") (class "Default")
      (node (ref "D255") (pin "1") (pinfunction "A_1") (pintype "passive"))
      (node (ref "S256") (pin "1") (pinfunction "1_1") (pintype "passive"))
    )
    (net (code "76") (name "Net-(D256-A)") (class "Default")
      (node (ref "D256") (pin "1") (pinfunction "A_1") (pintype "passive"))
      (node (ref "S269") (pin "1") (pinfunction "1_1") (pintype "passive"))
    )
    (net (code "77") (name "Net-(D257-A)") (class "Default")
      (node (ref "D257") (pin "1") (pinfunction "A_1") (pintype "passive"))
      (node (ref "S257") (pin "2") (pinfunction "2_2") (pintype "passive"))
    )
    (net (code "78") (name "Net-(D258-A)") (class "Default")
      (node (ref "D258") (pin "1") (pinfunction "A_1") (pintype "passive"))
      (node (ref "S258") (pin "1") (pinfunction "1_1") (pintype "passive"))
    )
    (net (code "79") (name "Net-(D259-A)") (class "Default")
      (node (ref "D259") (pin "1") (pinfunction "A_1") (pintype "passive"))
      (node (ref "S259") (pin "1") (pinfunction "1_1") (pintype "passive"))
    )
    (net (code "80") (name "Net-(D260-A)") (class "Default")
      (node (ref "D260") (pin "1") (pinfunction "A_1") (pintype "passive"))
      (node (ref "S260") (pin "1") (pinfunction "1_1") (pintype "passive"))
    )
    (net (code "81") (name "Net-(D261-A)") (class "Default")
      (node (ref "D261") (pin "1") (pinfunction "A_1") (pintype "passive"))
      (node (ref "S261") (pin "1") (pinfunction "1_1") (pintype "passive"))
      (node (ref "S261_1") (pin "1") (pinfunction "1_1") (pintype "passive"))
    )
    (net (code "82") (name "Net-(D262-A)") (class "Default")
      (node (ref "D262") (pin "1") (pinfunction "A_1") (pintype "passive"))
      (node (ref "S262") (pin "2") (pinfunction "2_2") (pintype "passive"))
    )
    (net (code "83") (name "Net-(D263-A)") (class "Default")
      (node (ref "D263") (pin "1") (pinfunction "A_1") (pintype "passive"))
      (node (ref "S263") (pin "2") (pinfunction "2_2") (pintype "passive"))
      (node (ref "S263_1") (pin "2") (pinfunction "2_2") (pintype "passive"))
    )
    (net (code "84") (name "Net-(D264-A)") (class "Default")
      (node (ref "D264") (pin "1") (pinfunction "A_1") (pintype "passive"))
      (node (ref "S264") (pin "1") (pinfunction "1_1") (pintype "passive"))
    )
    (net (code "85") (name "Net-(D265-A)") (class "Default")
      (node (ref "D265") (pin "1") (pinfunction "A_1") (pintype "passive"))
      (node (ref "S265") (pin "2") (pinfunction "2_2") (pintype "passive"))
    )
    (net (code "86") (name "Net-(D266-A)") (class "Default")
      (node (ref "D266") (pin "1") (pinfunction "A_1") (pintype "passive"))
      (node (ref "S266") (pin "1") (pinfunction "1_1") (pintype "passive"))
    )
    (net (code "87") (name "unconnected-(STAB1-Pad1)") (class "Default")
      (node (ref "STAB1") (pin "1") (pinfunction "1_1") (pintype "passive"))
    )
  )
)
